# Reciever.net
KiCad netlist of a schematic drawn in EAGLE
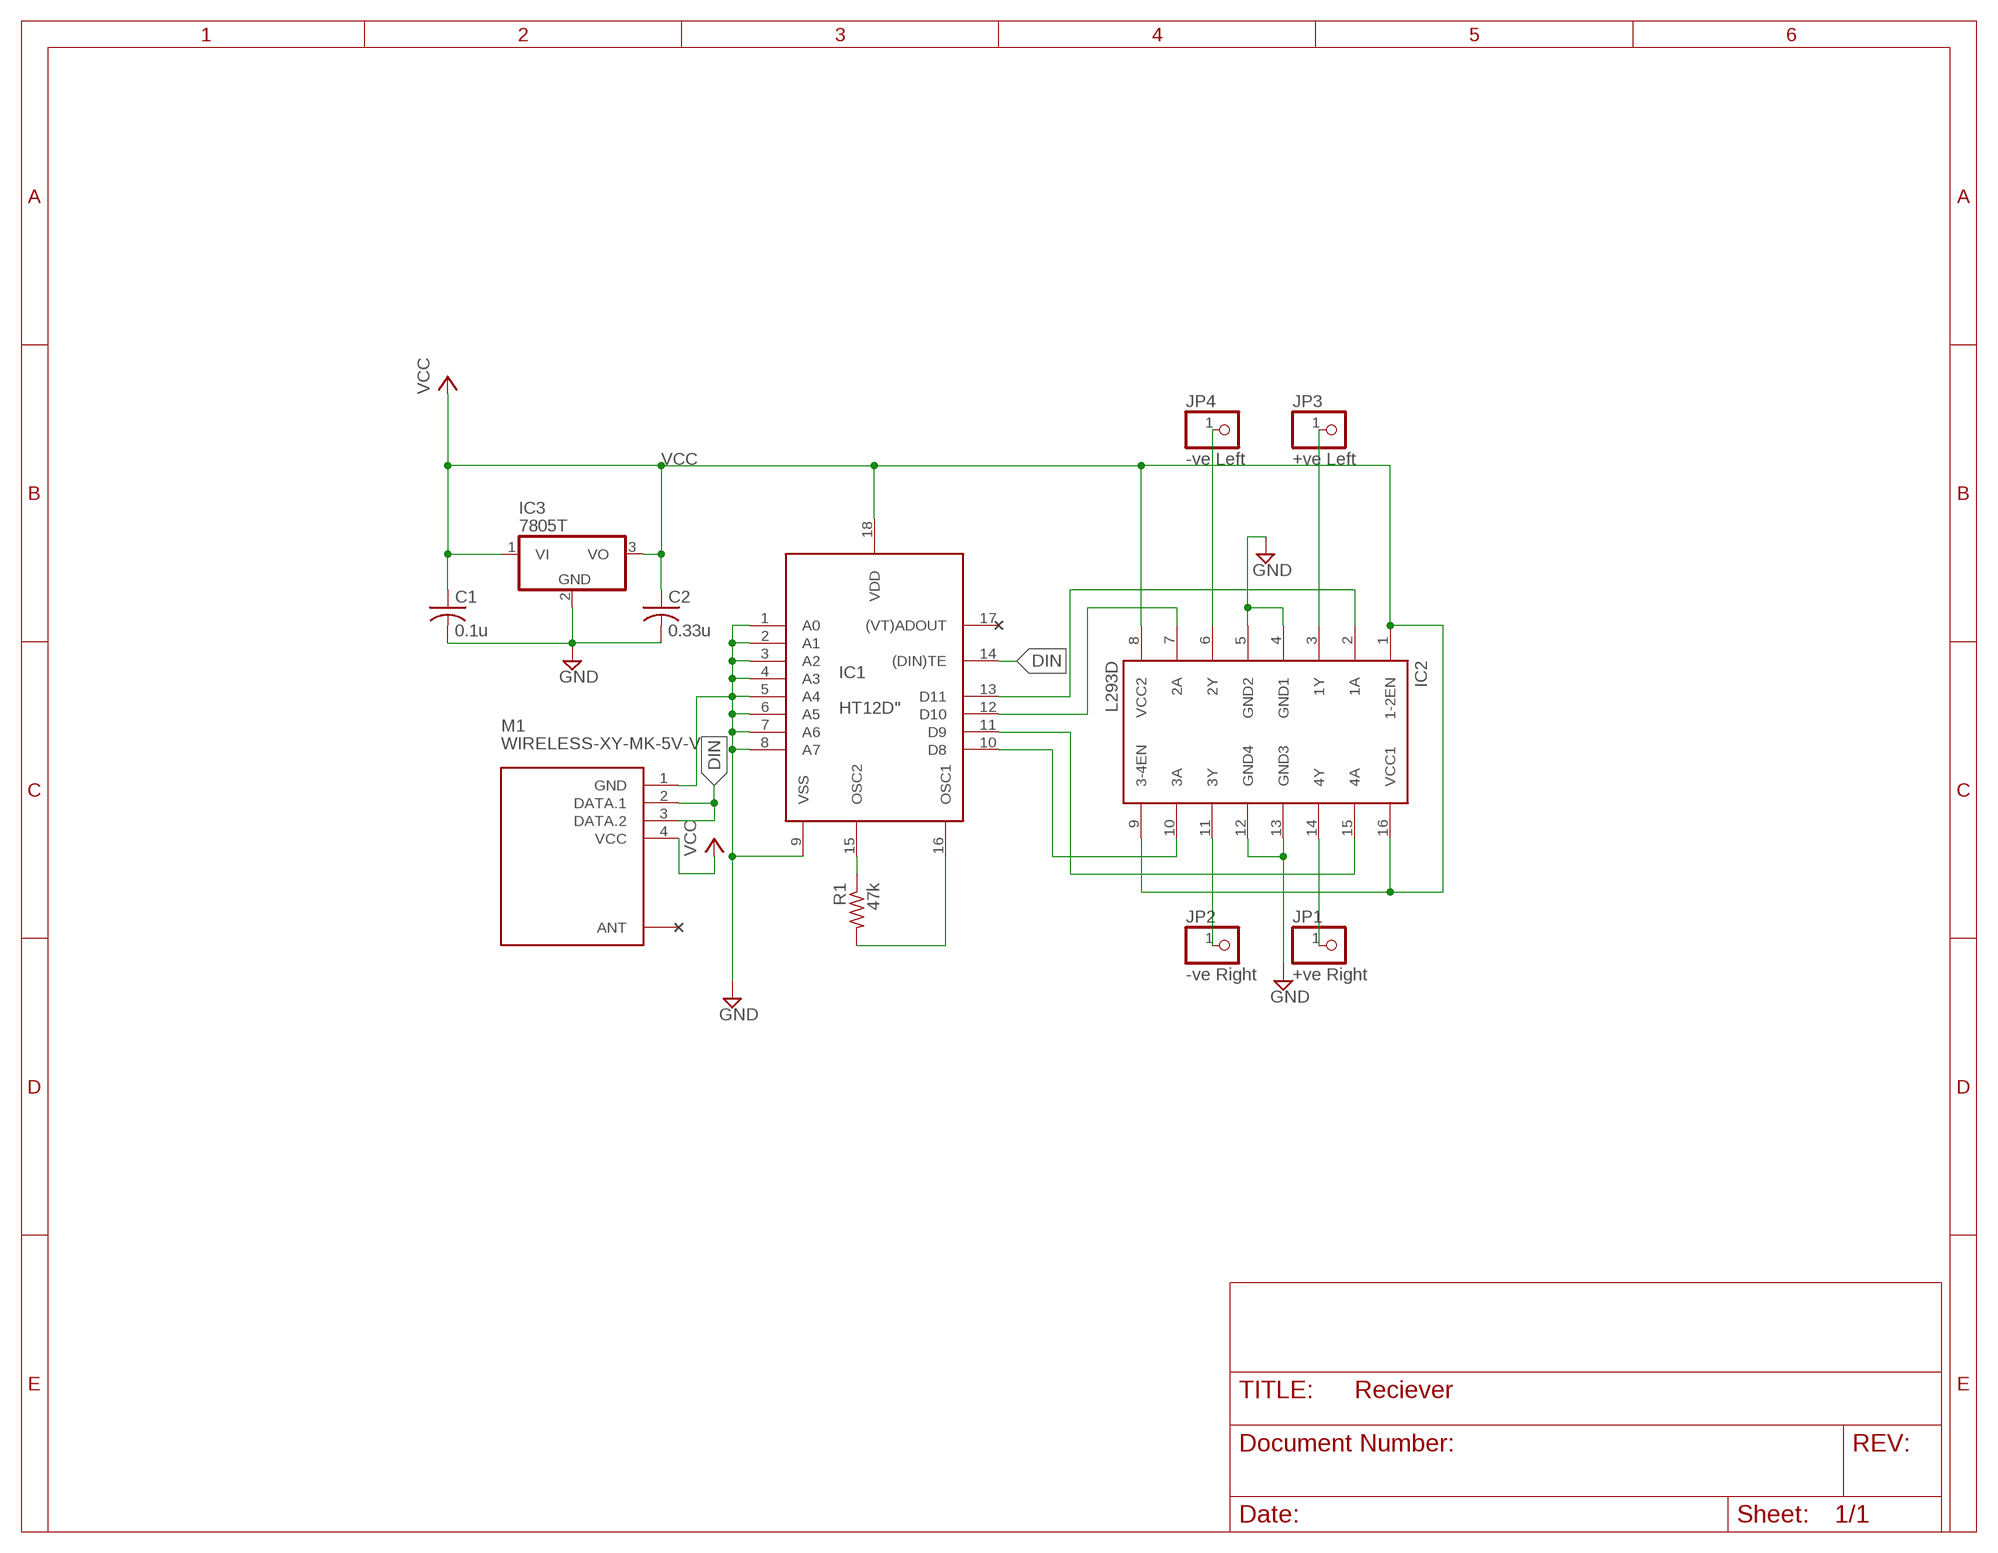
[diagram p0: schematic, sheet 1]

(export (version "E")
  (design (tool "Eeschema 10.0.6"))
  (components
    (comp (ref "C1")
      (value "0.1u")
      (footprint "eagle-import:C0805")
      (libsource (lib "eagle-import") (part "C-USC0805"))
    )
    (comp (ref "C2")
      (value "0.33u")
      (footprint "eagle-import:C0805")
      (libsource (lib "eagle-import") (part "C-USC0805"))
    )
    (comp (ref "IC1")
      (value "HT12D\"")
      (footprint "eagle-import:18-DIP-A")
      (libsource (lib "eagle-import") (part "HT12D{dblquote}"))
    )
    (comp (ref "IC2")
      (value "L293D")
      (footprint "eagle-import:DIL16")
      (libsource (lib "eagle-import") (part "L293D"))
    )
    (comp (ref "IC3")
      (value "7805T")
      (footprint "eagle-import:TO220H")
      (libsource (lib "eagle-import") (part "78T05"))
    )
    (comp (ref "JP1")
      (value "+ve Right")
      (footprint "eagle-import:1X01")
      (libsource (lib "eagle-import") (part "PINHD-1X1"))
    )
    (comp (ref "JP2")
      (value "-ve Right")
      (footprint "eagle-import:1X01")
      (libsource (lib "eagle-import") (part "PINHD-1X1"))
    )
    (comp (ref "JP3")
      (value "+ve Left")
      (footprint "eagle-import:1X01")
      (libsource (lib "eagle-import") (part "PINHD-1X1"))
    )
    (comp (ref "JP4")
      (value "-ve Left")
      (footprint "eagle-import:1X01")
      (libsource (lib "eagle-import") (part "PINHD-1X1"))
    )
    (comp (ref "M1")
      (value "WIRELESS-XY-MK-5V-V")
      (footprint "eagle-import:WIRELESS-XY-MK-5V#V")
      (libsource (lib "eagle-import") (part "WIRELESS-XY-MK-5V-V"))
    )
    (comp (ref "R1")
      (value "47k")
      (footprint "eagle-import:R0805")
      (libsource (lib "eagle-import") (part "R-US_R0805"))
    )
  )
  (nets
    (net (code "1") (name "DIN") (class "Default")
      (node (ref "IC1") (pin "14") (pinfunction "(DIN)TE_14") (pintype "input"))
      (node (ref "M1") (pin "2") (pinfunction "DATA.1_2") (pintype "bidirectional"))
      (node (ref "M1") (pin "3") (pinfunction "DATA.2_3") (pintype "bidirectional"))
    )
    (net (code "2") (name "GND") (class "Default")
      (node (ref "C1") (pin "2") (pinfunction "2_2") (pintype "passive"))
      (node (ref "C2") (pin "2") (pinfunction "2_2") (pintype "passive"))
      (node (ref "IC1") (pin "1") (pinfunction "A0_1") (pintype "input"))
      (node (ref "IC1") (pin "2") (pinfunction "A1_2") (pintype "input"))
      (node (ref "IC1") (pin "3") (pinfunction "A2_3") (pintype "input"))
      (node (ref "IC1") (pin "4") (pinfunction "A3_4") (pintype "input"))
      (node (ref "IC1") (pin "5") (pinfunction "A4_5") (pintype "input"))
      (node (ref "IC1") (pin "6") (pinfunction "A5_6") (pintype "input"))
      (node (ref "IC1") (pin "7") (pinfunction "A6_7") (pintype "input"))
      (node (ref "IC1") (pin "8") (pinfunction "A7_8") (pintype "input"))
      (node (ref "IC1") (pin "9") (pinfunction "VSS_9") (pintype "power_in"))
      (node (ref "IC2") (pin "12") (pinfunction "GND4_12") (pintype "power_in"))
      (node (ref "IC2") (pin "13") (pinfunction "GND3_13") (pintype "power_in"))
      (node (ref "IC2") (pin "4") (pinfunction "GND1_4") (pintype "power_in"))
      (node (ref "IC2") (pin "5") (pinfunction "GND2_5") (pintype "power_in"))
      (node (ref "IC3") (pin "2") (pinfunction "GND_2") (pintype "passive"))
      (node (ref "M1") (pin "1") (pinfunction "GND_1") (pintype "bidirectional"))
    )
    (net (code "3") (name "Net-(IC1-D8)") (class "Default")
      (node (ref "IC1") (pin "10") (pinfunction "D8_10") (pintype "output"))
      (node (ref "IC2") (pin "10") (pinfunction "3A_10") (pintype "input"))
    )
    (net (code "4") (name "Net-(IC1-D9)") (class "Default")
      (node (ref "IC1") (pin "11") (pinfunction "D9_11") (pintype "output"))
      (node (ref "IC2") (pin "15") (pinfunction "4A_15") (pintype "input"))
    )
    (net (code "5") (name "Net-(IC1-D10)") (class "Default")
      (node (ref "IC1") (pin "12") (pinfunction "D10_12") (pintype "output"))
      (node (ref "IC2") (pin "7") (pinfunction "2A_7") (pintype "input"))
    )
    (net (code "6") (name "Net-(IC1-D11)") (class "Default")
      (node (ref "IC1") (pin "13") (pinfunction "D11_13") (pintype "output"))
      (node (ref "IC2") (pin "2") (pinfunction "1A_2") (pintype "input"))
    )
    (net (code "7") (name "Net-(IC1-OSC1)") (class "Default")
      (node (ref "IC1") (pin "16") (pinfunction "OSC1_16") (pintype "input"))
      (node (ref "R1") (pin "2") (pinfunction "2_2") (pintype "passive"))
    )
    (net (code "8") (name "Net-(IC1-OSC2)") (class "Default")
      (node (ref "IC1") (pin "15") (pinfunction "OSC2_15") (pintype "output"))
      (node (ref "R1") (pin "1") (pinfunction "1_1") (pintype "passive"))
    )
    (net (code "9") (name "Net-(IC2-1Y)") (class "Default")
      (node (ref "IC2") (pin "3") (pinfunction "1Y_3") (pintype "output"))
      (node (ref "JP3") (pin "1") (pinfunction "1_1") (pintype "passive"))
    )
    (net (code "10") (name "Net-(IC2-2Y)") (class "Default")
      (node (ref "IC2") (pin "6") (pinfunction "2Y_6") (pintype "output"))
      (node (ref "JP4") (pin "1") (pinfunction "1_1") (pintype "passive"))
    )
    (net (code "11") (name "Net-(IC2-3Y)") (class "Default")
      (node (ref "IC2") (pin "11") (pinfunction "3Y_11") (pintype "output"))
      (node (ref "JP2") (pin "1") (pinfunction "1_1") (pintype "passive"))
    )
    (net (code "12") (name "Net-(IC2-4Y)") (class "Default")
      (node (ref "IC2") (pin "14") (pinfunction "4Y_14") (pintype "output"))
      (node (ref "JP1") (pin "1") (pinfunction "1_1") (pintype "passive"))
    )
    (net (code "13") (name "VCC") (class "Default")
      (node (ref "C1") (pin "1") (pinfunction "1_1") (pintype "passive"))
      (node (ref "C2") (pin "1") (pinfunction "1_1") (pintype "passive"))
      (node (ref "IC1") (pin "18") (pinfunction "VDD_18") (pintype "power_in"))
      (node (ref "IC2") (pin "1") (pinfunction "1-2EN_1") (pintype "input"))
      (node (ref "IC2") (pin "16") (pinfunction "VCC1_16") (pintype "power_in"))
      (node (ref "IC2") (pin "8") (pinfunction "VCC2_8") (pintype "power_in"))
      (node (ref "IC2") (pin "9") (pinfunction "3-4EN_9") (pintype "input"))
      (node (ref "IC3") (pin "1") (pinfunction "VI_1") (pintype "input"))
      (node (ref "IC3") (pin "3") (pinfunction "VO_3") (pintype "passive"))
      (node (ref "M1") (pin "4") (pinfunction "VCC_4") (pintype "bidirectional"))
    )
    (net (code "14") (name "unconnected-(IC1-(VT)ADOUT-Pad17)") (class "Default")
      (node (ref "IC1") (pin "17") (pinfunction "(VT)ADOUT_17") (pintype "output"))
    )
    (net (code "15") (name "unconnected-(M1-PadANT)") (class "Default")
      (node (ref "M1") (pin "ANT") (pinfunction "ANT_ANT") (pintype "output"))
    )
  )
)
